# 4_adc.net
KiCad netlist of a schematic drawn in Altium Designer
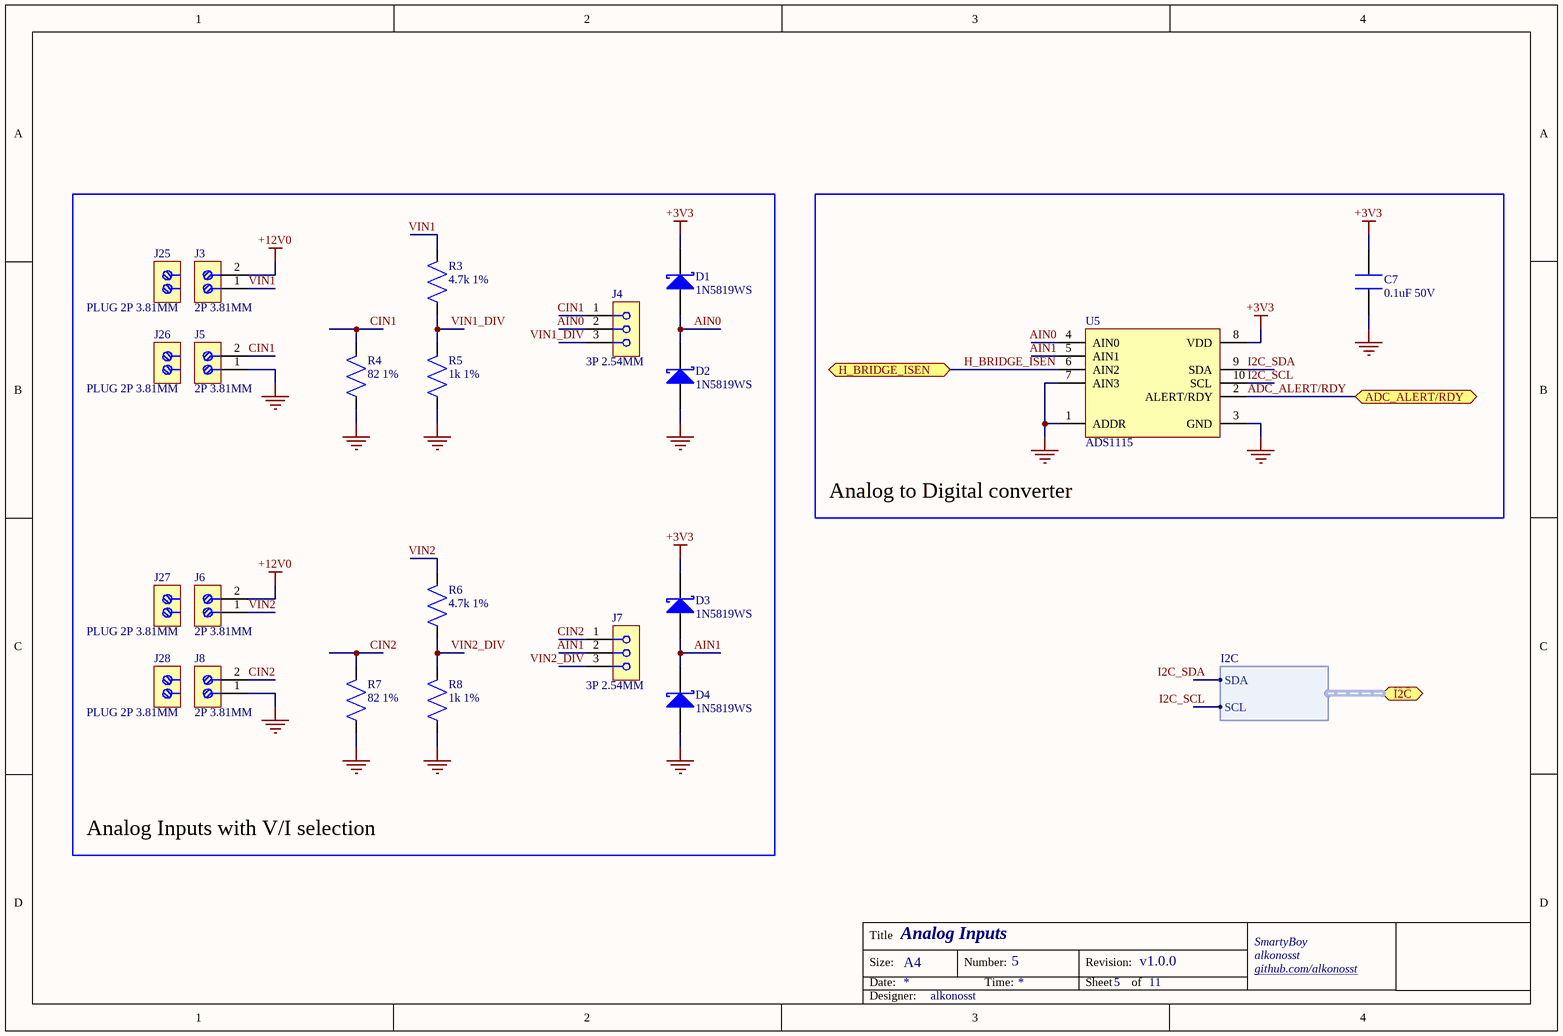
[diagram p0: 4_adc.SchDoc]

(export (version "E")
  (design (tool "Eeschema 10.0.6"))
  (components
    (comp (ref "C7")
      (value "0.1uF 50V")
      (footprint "C0603")
      (description "X7R 100nF ±10% 50V 0603 Multilayer Ceramic Capacitors MLCC - SMD/SMT")
      (fields (field (name "LCSC PART") "C14663"))
      (libsource (lib "nombre_por_definir") (part "CC0603KRX7R9BB104"))
    )
    (comp (ref "D1")
      (value "1N5819WS")
      (footprint "SOD-323")
      (description "40V 1A 600mV @ 1A SOD-323 Schottky Barrier Diodes (SBD)")
      (fields (field (name "LCSC PART") "C191023"))
      (libsource (lib "nombre_por_definir") (part "1N5819WS"))
    )
    (comp (ref "D2")
      (value "1N5819WS")
      (footprint "SOD-323")
      (description "40V 1A 600mV @ 1A SOD-323 Schottky Barrier Diodes (SBD)")
      (fields (field (name "LCSC PART") "C191023"))
      (libsource (lib "nombre_por_definir") (part "1N5819WS"))
    )
    (comp (ref "D3")
      (value "1N5819WS")
      (footprint "SOD-323")
      (description "40V 1A 600mV @ 1A SOD-323 Schottky Barrier Diodes (SBD)")
      (fields (field (name "LCSC PART") "C191023"))
      (libsource (lib "nombre_por_definir") (part "1N5819WS"))
    )
    (comp (ref "D4")
      (value "1N5819WS")
      (footprint "SOD-323")
      (description "40V 1A 600mV @ 1A SOD-323 Schottky Barrier Diodes (SBD)")
      (fields (field (name "LCSC PART") "C191023"))
      (libsource (lib "nombre_por_definir") (part "1N5819WS"))
    )
    (comp (ref "J3")
      (value "2P 3.81MM")
      (footprint "TB-2P-3.81MM")
      (description "Terminal Block 2 Positions 3.81MM")
      (libsource (lib "nombre_por_definir") (part "TBLOCK-2P-3.81MM"))
    )
    (comp (ref "J4")
      (value "3P 2.54MM")
      (footprint "HDR-M-3P-2.54MM")
      (description "3 2.54mm Straight 1 Header，Breakaway Through Hole Pin Header & Female Header")
      (fields (field (name "LCSC PART") "C49257"))
      (libsource (lib "nombre_por_definir") (part "C49257"))
    )
    (comp (ref "J5")
      (value "2P 3.81MM")
      (footprint "TB-2P-3.81MM")
      (description "Terminal Block 2 Positions 3.81MM")
      (libsource (lib "nombre_por_definir") (part "TBLOCK-2P-3.81MM"))
    )
    (comp (ref "J6")
      (value "2P 3.81MM")
      (footprint "TB-2P-3.81MM")
      (description "Terminal Block 2 Positions 3.81MM")
      (libsource (lib "nombre_por_definir") (part "TBLOCK-2P-3.81MM"))
    )
    (comp (ref "J7")
      (value "3P 2.54MM")
      (footprint "HDR-M-3P-2.54MM")
      (description "3 2.54mm Straight 1 Header，Breakaway Through Hole Pin Header & Female Header")
      (fields (field (name "LCSC PART") "C49257"))
      (libsource (lib "nombre_por_definir") (part "C49257"))
    )
    (comp (ref "J8")
      (value "2P 3.81MM")
      (footprint "TB-2P-3.81MM")
      (description "Terminal Block 2 Positions 3.81MM")
      (libsource (lib "nombre_por_definir") (part "TBLOCK-2P-3.81MM"))
    )
    (comp (ref "J25")
      (value "PLUG 2P 3.81MM")
      (footprint "TB-PLUG-2P-3.81MM")
      (description "Terminal block plug 2positions 3.81mm")
      (libsource (lib "nombre_por_definir") (part "PLUG-2P-3.81MM"))
    )
    (comp (ref "J26")
      (value "PLUG 2P 3.81MM")
      (footprint "TB-PLUG-2P-3.81MM")
      (description "Terminal block plug 2positions 3.81mm")
      (libsource (lib "nombre_por_definir") (part "PLUG-2P-3.81MM"))
    )
    (comp (ref "J27")
      (value "PLUG 2P 3.81MM")
      (footprint "TB-PLUG-2P-3.81MM")
      (description "Terminal block plug 2positions 3.81mm")
      (libsource (lib "nombre_por_definir") (part "PLUG-2P-3.81MM"))
    )
    (comp (ref "J28")
      (value "PLUG 2P 3.81MM")
      (footprint "TB-PLUG-2P-3.81MM")
      (description "Terminal block plug 2positions 3.81mm")
      (libsource (lib "nombre_por_definir") (part "PLUG-2P-3.81MM"))
    )
    (comp (ref "R3")
      (value "4.7k 1%")
      (footprint "R0603")
      (description "±1% 4.7kΩ ±100ppm/℃ 0.1W 0603 Chip Resistor - Surface Mount")
      (fields (field (name "LCSC PART") "C23162"))
      (libsource (lib "nombre_por_definir") (part "0603WAF4701T5E"))
    )
    (comp (ref "R4")
      (value "82 1%")
      (footprint "R0603")
      (description "82Ω ±1% ±200ppm/℃ 0.1W 0603 Chip Resistor - Surface Mount")
      (fields (field (name "LCSC PART") "C23255"))
      (libsource (lib "nombre_por_definir") (part "0603WAF820JT5E"))
    )
    (comp (ref "R5")
      (value "1k 1%")
      (footprint "R0603")
      (description "±1% ±100ppm/℃ 1kΩ 0.1W 0603 Chip Resistor - Surface Mount")
      (fields (field (name "LCSC PART") "C21190"))
      (libsource (lib "nombre_por_definir") (part "0603WAF1001T5E"))
    )
    (comp (ref "R6")
      (value "4.7k 1%")
      (footprint "R0603")
      (description "±1% 4.7kΩ ±100ppm/℃ 0.1W 0603 Chip Resistor - Surface Mount")
      (fields (field (name "LCSC PART") "C23162"))
      (libsource (lib "nombre_por_definir") (part "0603WAF4701T5E"))
    )
    (comp (ref "R7")
      (value "82 1%")
      (footprint "R0603")
      (description "82Ω ±1% ±200ppm/℃ 0.1W 0603 Chip Resistor - Surface Mount")
      (fields (field (name "LCSC PART") "C23255"))
      (libsource (lib "nombre_por_definir") (part "0603WAF820JT5E"))
    )
    (comp (ref "R8")
      (value "1k 1%")
      (footprint "R0603")
      (description "±1% ±100ppm/℃ 1kΩ 0.1W 0603 Chip Resistor - Surface Mount")
      (fields (field (name "LCSC PART") "C21190"))
      (libsource (lib "nombre_por_definir") (part "0603WAF1001T5E"))
    )
    (comp (ref "U5")
      (value "ADS1115")
      (footprint "MSOP-10")
      (description "2,4 Differential, Single Ended 16 860 VSSOP-10 Analog To Digital Converters (ADCs)")
      (fields (field (name "LCSC PART") "C37593"))
      (libsource (lib "nombre_por_definir") (part "ADS1115IDGSR"))
    )
  )
  (nets
    (net (code "2") (name "+3V3") (class "Default")
      (node (ref "C7") (pin "1") (pinfunction "1_1") (pintype "passive"))
      (node (ref "D1") (pin "1") (pinfunction "K_1") (pintype "passive"))
      (node (ref "D3") (pin "1") (pinfunction "K_1") (pintype "passive"))
      (node (ref "U5") (pin "8") (pinfunction "VDD_8") (pintype "passive"))
    )
    (net (code "3") (name "+12V0") (class "Default")
      (node (ref "J3") (pin "2") (pinfunction "2_2") (pintype "passive"))
      (node (ref "J6") (pin "2") (pinfunction "2_2") (pintype "passive"))
    )
    (net (code "4") (name "/ADC_ALERT{slash}RDY") (class "Default")
      (node (ref "U5") (pin "2") (pinfunction "ALERT/RDY_2") (pintype "passive"))
    )
    (net (code "5") (name "/AIN0") (class "Default")
      (node (ref "D1") (pin "2") (pinfunction "A_2") (pintype "passive"))
      (node (ref "D2") (pin "1") (pinfunction "K_1") (pintype "passive"))
      (node (ref "J4") (pin "2") (pinfunction "2_2") (pintype "passive"))
      (node (ref "U5") (pin "4") (pinfunction "AIN0_4") (pintype "passive"))
    )
    (net (code "6") (name "/AIN1") (class "Default")
      (node (ref "D3") (pin "2") (pinfunction "A_2") (pintype "passive"))
      (node (ref "D4") (pin "1") (pinfunction "K_1") (pintype "passive"))
      (node (ref "J7") (pin "2") (pinfunction "2_2") (pintype "passive"))
      (node (ref "U5") (pin "5") (pinfunction "AIN1_5") (pintype "passive"))
    )
    (net (code "7") (name "/CIN1") (class "Default")
      (node (ref "J4") (pin "1") (pinfunction "1_1") (pintype "passive"))
      (node (ref "J5") (pin "2") (pinfunction "2_2") (pintype "passive"))
      (node (ref "R4") (pin "2") (pinfunction "2_2") (pintype "passive"))
    )
    (net (code "8") (name "/CIN2") (class "Default")
      (node (ref "J7") (pin "1") (pinfunction "1_1") (pintype "passive"))
      (node (ref "J8") (pin "2") (pinfunction "2_2") (pintype "passive"))
      (node (ref "R7") (pin "2") (pinfunction "2_2") (pintype "passive"))
    )
    (net (code "9") (name "/H_BRIDGE_ISEN") (class "Default")
      (node (ref "U5") (pin "6") (pinfunction "AIN2_6") (pintype "passive"))
    )
    (net (code "10") (name "/I2C_SCL") (class "Default")
      (node (ref "U5") (pin "10") (pinfunction "SCL_10") (pintype "passive"))
    )
    (net (code "11") (name "/I2C_SDA") (class "Default")
      (node (ref "U5") (pin "9") (pinfunction "SDA_9") (pintype "passive"))
    )
    (net (code "12") (name "/VIN1") (class "Default")
      (node (ref "J3") (pin "1") (pinfunction "1_1") (pintype "passive"))
      (node (ref "R3") (pin "2") (pinfunction "2_2") (pintype "passive"))
    )
    (net (code "13") (name "/VIN1_DIV") (class "Default")
      (node (ref "J4") (pin "3") (pinfunction "3_3") (pintype "passive"))
      (node (ref "R3") (pin "1") (pinfunction "1_1") (pintype "passive"))
      (node (ref "R5") (pin "2") (pinfunction "2_2") (pintype "passive"))
    )
    (net (code "14") (name "/VIN2") (class "Default")
      (node (ref "J6") (pin "1") (pinfunction "1_1") (pintype "passive"))
      (node (ref "R6") (pin "2") (pinfunction "2_2") (pintype "passive"))
    )
    (net (code "15") (name "/VIN2_DIV") (class "Default")
      (node (ref "J7") (pin "3") (pinfunction "3_3") (pintype "passive"))
      (node (ref "R6") (pin "1") (pinfunction "1_1") (pintype "passive"))
      (node (ref "R8") (pin "2") (pinfunction "2_2") (pintype "passive"))
    )
    (net (code "17") (name "GND") (class "Default")
      (node (ref "C7") (pin "2") (pinfunction "2_2") (pintype "passive"))
      (node (ref "D2") (pin "2") (pinfunction "A_2") (pintype "passive"))
      (node (ref "D4") (pin "2") (pinfunction "A_2") (pintype "passive"))
      (node (ref "J5") (pin "1") (pinfunction "1_1") (pintype "passive"))
      (node (ref "J8") (pin "1") (pinfunction "1_1") (pintype "passive"))
      (node (ref "R4") (pin "1") (pinfunction "1_1") (pintype "passive"))
      (node (ref "R5") (pin "1") (pinfunction "1_1") (pintype "passive"))
      (node (ref "R7") (pin "1") (pinfunction "1_1") (pintype "passive"))
      (node (ref "R8") (pin "1") (pinfunction "1_1") (pintype "passive"))
      (node (ref "U5") (pin "1") (pinfunction "ADDR_1") (pintype "passive"))
      (node (ref "U5") (pin "3") (pinfunction "GND_3") (pintype "passive"))
      (node (ref "U5") (pin "7") (pinfunction "AIN3_7") (pintype "passive"))
    )
  )
)
